# Vitulus_mower_control_2021-01-18.net
KiCad netlist of a schematic drawn in EasyEDA
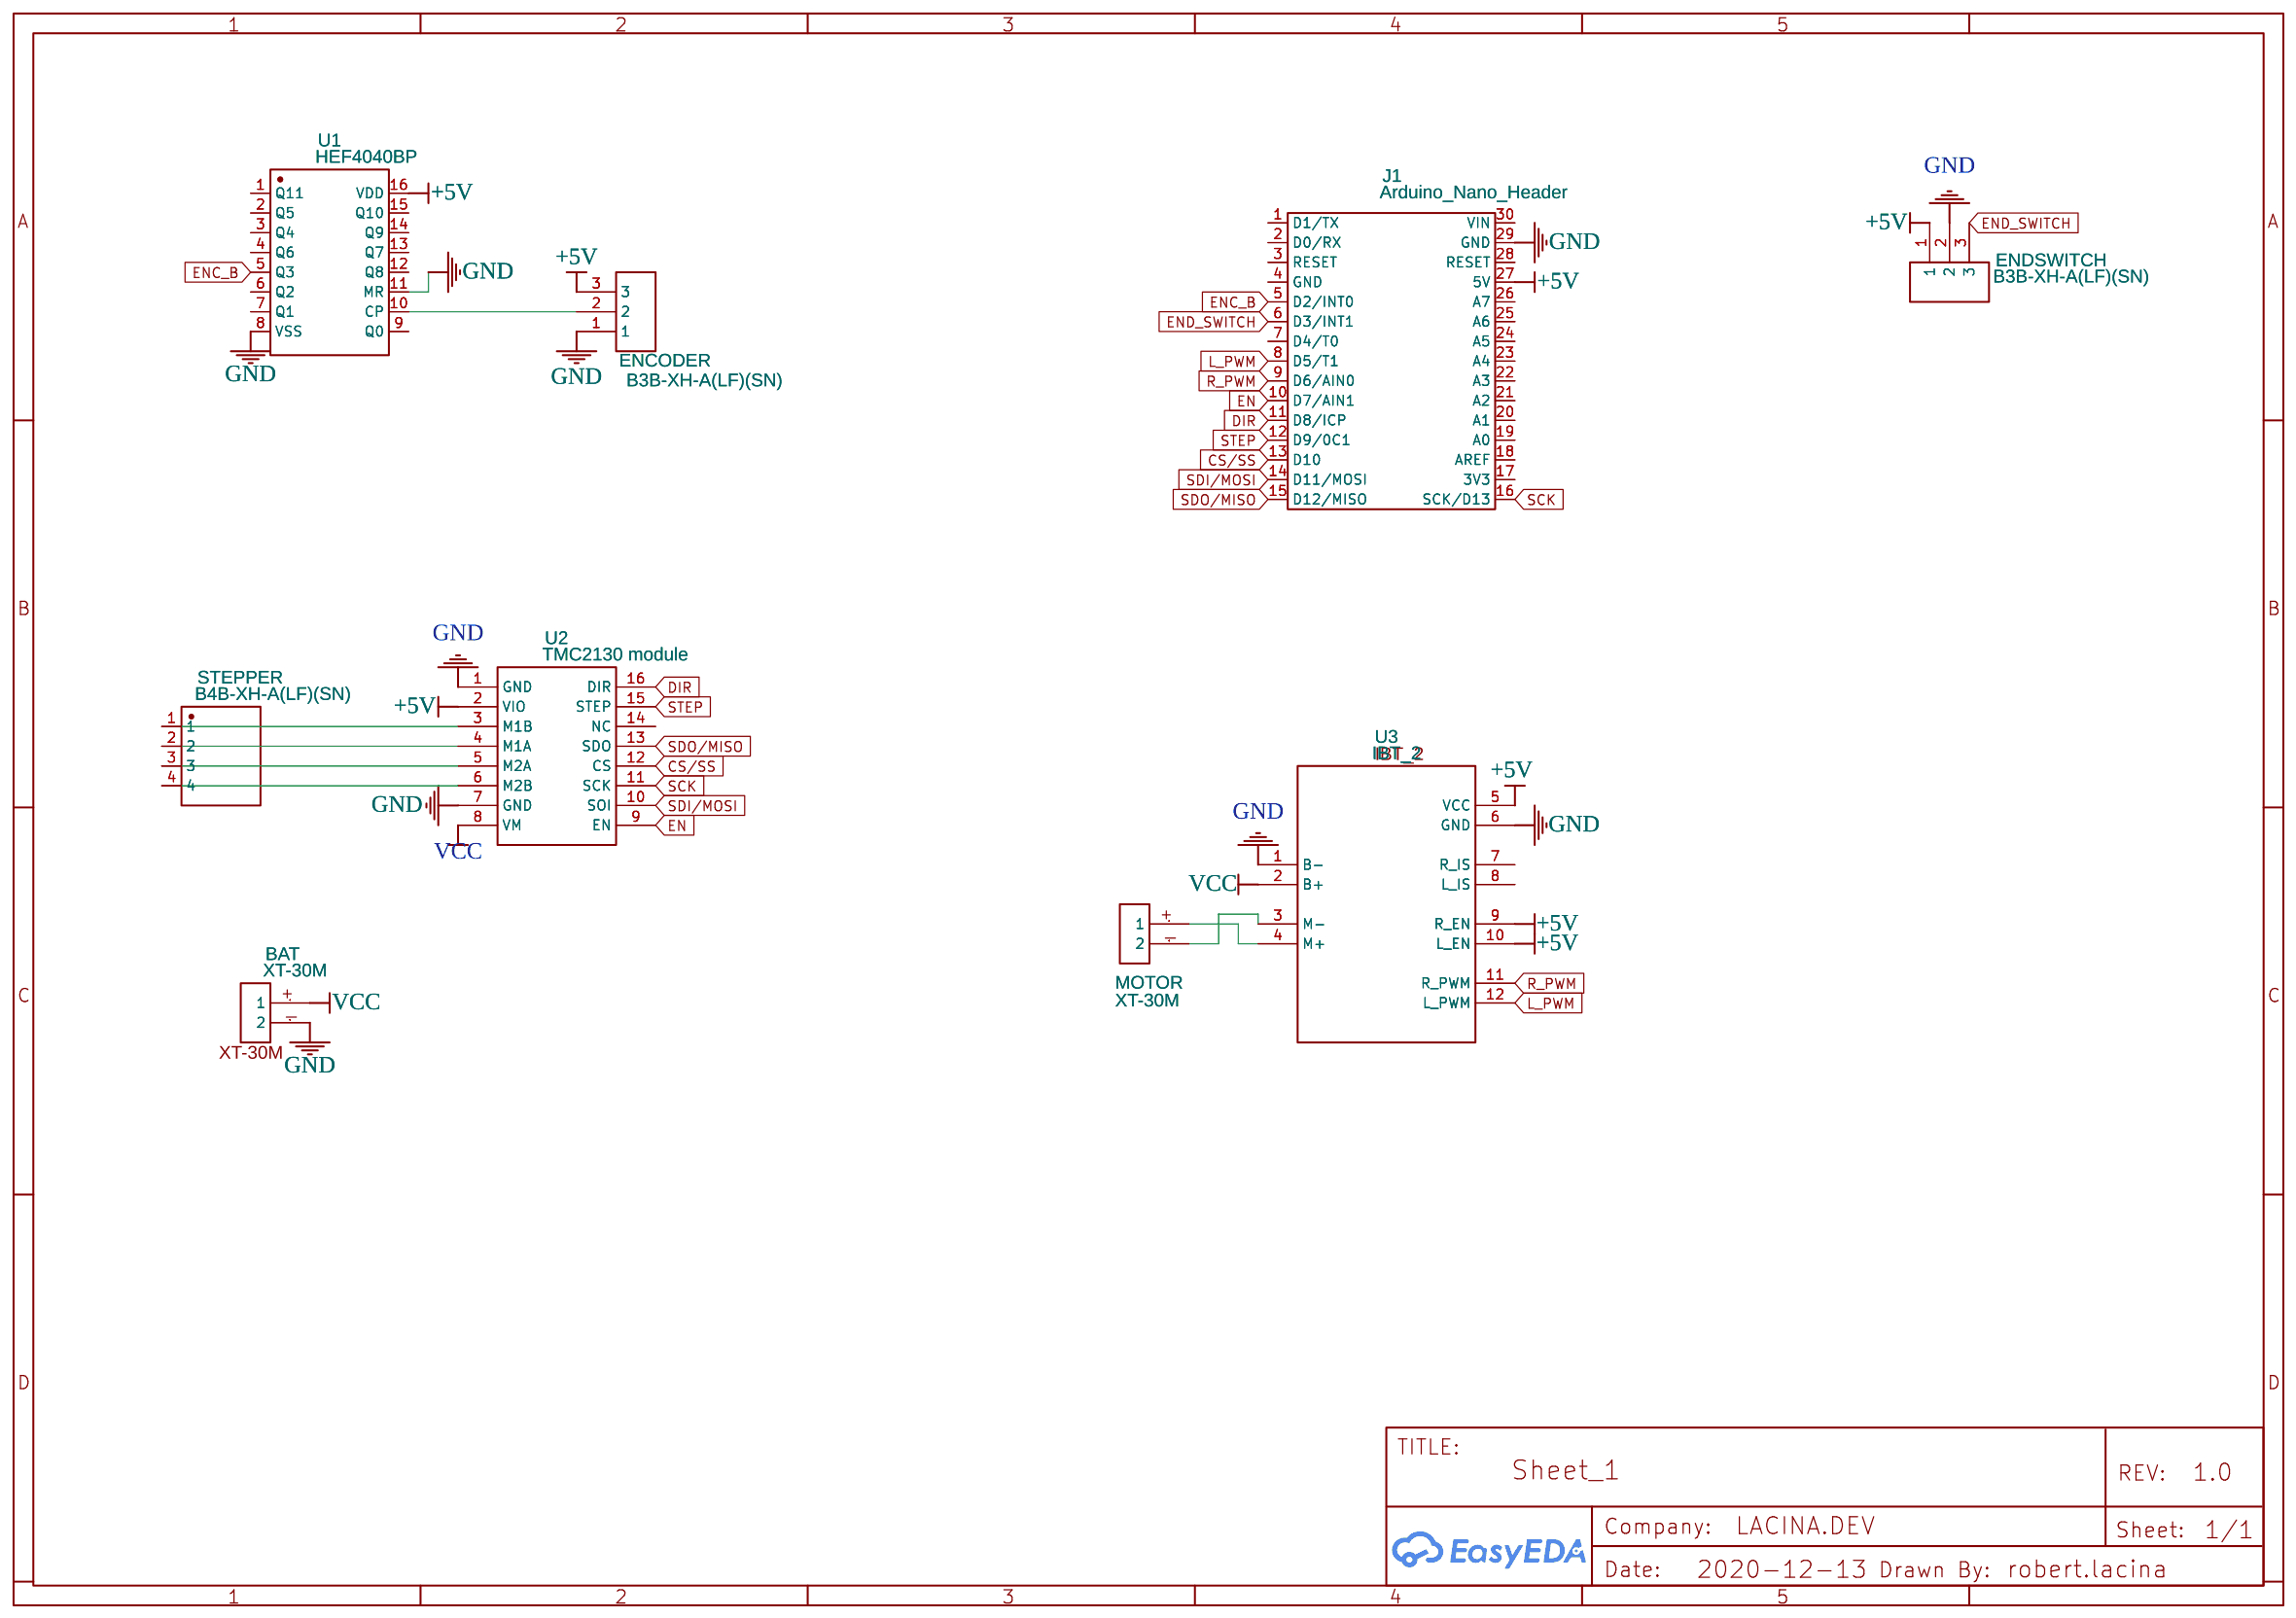
[diagram p0: schematic sheet]

(export (version "E")
  (design (tool "Eeschema 10.0.6"))
  (components
    (comp (ref "BAT") (value "XT-30M") (libsource (lib "") (part "XT-30M_1")))
    (comp (ref "ENCODER")
      (value "B3B-XH-A(LF)(SN)")
      (fields (field (name "BOM_Supplier Part") "C144394"))
      (libsource (lib "") (part "B3B-XH-A(LF)(SN)_1"))
    )
    (comp (ref "ENDSWITCH")
      (value "B3B-XH-A(LF)(SN)")
      (fields (field (name "BOM_Supplier Part") "C144394"))
      (libsource (lib "") (part "B3B-XH-A(LF)(SN)"))
    )
    (comp (ref "J1") (value "Arduino_Nano_Header") (libsource (lib "") (part "Arduino_Nano_Header")))
    (comp (ref "MOTOR") (value "XT-30M") (libsource (lib "") (part "XT-30M")))
    (comp (ref "STEPPER")
      (value "B4B-XH-A(LF)(SN)")
      (fields (field (name "BOM_Supplier Part") "C144395"))
      (libsource (lib "") (part "B4B-XH-A(LF)(SN)"))
    )
    (comp (ref "U1") (value "HEF4040BP") (libsource (lib "") (part "HEF4040BP")))
    (comp (ref "U2") (value "TMC2130 module") (libsource (lib "") (part "TMC2130 module")))
    (comp (ref "U3") (value "IBT_2") (libsource (lib "") (part "IBT_2")))
  )
  (nets
    (net (code "1") (name "+5V") (class "Default")
      (node (ref "ENCODER") (pin "3") (pinfunction "3_3") (pintype "unspecified"))
      (node (ref "ENDSWITCH") (pin "1") (pinfunction "1_1") (pintype "unspecified"))
      (node (ref "J1") (pin "27") (pinfunction "5V_27") (pintype "unspecified"))
      (node (ref "U1") (pin "16") (pinfunction "VDD_16") (pintype "unspecified"))
      (node (ref "U2") (pin "2") (pinfunction "VIO_2") (pintype "unspecified"))
      (node (ref "U3") (pin "10") (pinfunction "L_EN_10") (pintype "unspecified"))
      (node (ref "U3") (pin "5") (pinfunction "VCC_5") (pintype "unspecified"))
      (node (ref "U3") (pin "9") (pinfunction "R_EN_9") (pintype "unspecified"))
    )
    (net (code "2") (name "CS{slash}SS") (class "Default")
      (node (ref "J1") (pin "13") (pinfunction "D10_13") (pintype "unspecified"))
      (node (ref "U2") (pin "12") (pinfunction "CS_12") (pintype "unspecified"))
    )
    (net (code "3") (name "DIR") (class "Default")
      (node (ref "J1") (pin "11") (pinfunction "D8/ICP_11") (pintype "unspecified"))
      (node (ref "U2") (pin "16") (pinfunction "DIR_16") (pintype "unspecified"))
    )
    (net (code "4") (name "EN") (class "Default")
      (node (ref "J1") (pin "10") (pinfunction "D7/AIN1_10") (pintype "unspecified"))
      (node (ref "U2") (pin "9") (pinfunction "EN_9") (pintype "unspecified"))
    )
    (net (code "5") (name "ENC_B") (class "Default")
      (node (ref "J1") (pin "5") (pinfunction "D2/INT0_5") (pintype "unspecified"))
      (node (ref "U1") (pin "5") (pinfunction "Q3_5") (pintype "unspecified"))
    )
    (net (code "6") (name "END_SWITCH") (class "Default")
      (node (ref "ENDSWITCH") (pin "3") (pinfunction "3_3") (pintype "unspecified"))
      (node (ref "J1") (pin "6") (pinfunction "D3/INT1_6") (pintype "unspecified"))
    )
    (net (code "7") (name "GND") (class "Default")
      (node (ref "BAT") (pin "2") (pinfunction "2_2") (pintype "unspecified"))
      (node (ref "ENCODER") (pin "1") (pinfunction "1_1") (pintype "unspecified"))
      (node (ref "ENDSWITCH") (pin "2") (pinfunction "2_2") (pintype "unspecified"))
      (node (ref "J1") (pin "29") (pinfunction "GND_29") (pintype "unspecified"))
      (node (ref "U1") (pin "11") (pinfunction "MR_11") (pintype "unspecified"))
      (node (ref "U1") (pin "8") (pinfunction "VSS_8") (pintype "unspecified"))
      (node (ref "U2") (pin "1") (pinfunction "GND_1") (pintype "unspecified"))
      (node (ref "U2") (pin "7") (pinfunction "GND_7") (pintype "unspecified"))
      (node (ref "U3") (pin "1") (pinfunction "B-_1") (pintype "unspecified"))
      (node (ref "U3") (pin "6") (pinfunction "GND_6") (pintype "unspecified"))
    )
    (net (code "8") (name "L_PWM") (class "Default")
      (node (ref "J1") (pin "8") (pinfunction "D5/T1_8") (pintype "unspecified"))
      (node (ref "U3") (pin "12") (pinfunction "L_PWM_12") (pintype "unspecified"))
    )
    (net (code "9") (name "Net-(U1-CP)") (class "Default")
      (node (ref "ENCODER") (pin "2") (pinfunction "2_2") (pintype "unspecified"))
      (node (ref "U1") (pin "10") (pinfunction "CP_10") (pintype "unspecified"))
    )
    (net (code "10") (name "Net-(U2-M1A)") (class "Default")
      (node (ref "STEPPER") (pin "2") (pinfunction "2_2") (pintype "unspecified"))
      (node (ref "U2") (pin "4") (pinfunction "M1A_4") (pintype "unspecified"))
    )
    (net (code "11") (name "Net-(U2-M1B)") (class "Default")
      (node (ref "STEPPER") (pin "1") (pinfunction "1_1") (pintype "unspecified"))
      (node (ref "U2") (pin "3") (pinfunction "M1B_3") (pintype "unspecified"))
    )
    (net (code "12") (name "Net-(U2-M2A)") (class "Default")
      (node (ref "STEPPER") (pin "3") (pinfunction "3_3") (pintype "unspecified"))
      (node (ref "U2") (pin "5") (pinfunction "M2A_5") (pintype "unspecified"))
    )
    (net (code "13") (name "Net-(U2-M2B)") (class "Default")
      (node (ref "STEPPER") (pin "4") (pinfunction "4_4") (pintype "unspecified"))
      (node (ref "U2") (pin "6") (pinfunction "M2B_6") (pintype "unspecified"))
    )
    (net (code "14") (name "Net-(U3-M+)") (class "Default")
      (node (ref "MOTOR") (pin "1") (pinfunction "1_1") (pintype "unspecified"))
      (node (ref "U3") (pin "4") (pinfunction "M+_4") (pintype "unspecified"))
    )
    (net (code "15") (name "Net-(U3-M-)") (class "Default")
      (node (ref "MOTOR") (pin "2") (pinfunction "2_2") (pintype "unspecified"))
      (node (ref "U3") (pin "3") (pinfunction "M-_3") (pintype "unspecified"))
    )
    (net (code "16") (name "R_PWM") (class "Default")
      (node (ref "J1") (pin "9") (pinfunction "D6/AIN0_9") (pintype "unspecified"))
      (node (ref "U3") (pin "11") (pinfunction "R_PWM_11") (pintype "unspecified"))
    )
    (net (code "17") (name "SCK") (class "Default")
      (node (ref "J1") (pin "16") (pinfunction "SCK/D13_16") (pintype "unspecified"))
      (node (ref "U2") (pin "11") (pinfunction "SCK_11") (pintype "unspecified"))
    )
    (net (code "18") (name "SDI{slash}MOSI") (class "Default")
      (node (ref "J1") (pin "14") (pinfunction "D11/MOSI_14") (pintype "unspecified"))
      (node (ref "U2") (pin "10") (pinfunction "SOI_10") (pintype "unspecified"))
    )
    (net (code "19") (name "SDO{slash}MISO") (class "Default")
      (node (ref "J1") (pin "15") (pinfunction "D12/MISO_15") (pintype "unspecified"))
      (node (ref "U2") (pin "13") (pinfunction "SDO_13") (pintype "unspecified"))
    )
    (net (code "20") (name "STEP") (class "Default")
      (node (ref "J1") (pin "12") (pinfunction "D9/0C1_12") (pintype "unspecified"))
      (node (ref "U2") (pin "15") (pinfunction "STEP_15") (pintype "unspecified"))
    )
    (net (code "21") (name "VCC") (class "Default")
      (node (ref "BAT") (pin "1") (pinfunction "1_1") (pintype "unspecified"))
      (node (ref "U2") (pin "8") (pinfunction "VM_8") (pintype "unspecified"))
      (node (ref "U3") (pin "2") (pinfunction "B+_2") (pintype "unspecified"))
    )
    (net (code "22") (name "unconnected-(J1-3V3-Pad17)") (class "Default")
      (node (ref "J1") (pin "17") (pinfunction "3V3_17") (pintype "unspecified"))
    )
    (net (code "23") (name "unconnected-(J1-A0-Pad19)") (class "Default")
      (node (ref "J1") (pin "19") (pinfunction "A0_19") (pintype "unspecified"))
    )
    (net (code "24") (name "unconnected-(J1-A1-Pad20)") (class "Default")
      (node (ref "J1") (pin "20") (pinfunction "A1_20") (pintype "unspecified"))
    )
    (net (code "25") (name "unconnected-(J1-A2-Pad21)") (class "Default")
      (node (ref "J1") (pin "21") (pinfunction "A2_21") (pintype "unspecified"))
    )
    (net (code "26") (name "unconnected-(J1-A3-Pad22)") (class "Default")
      (node (ref "J1") (pin "22") (pinfunction "A3_22") (pintype "unspecified"))
    )
    (net (code "27") (name "unconnected-(J1-A4-Pad23)") (class "Default")
      (node (ref "J1") (pin "23") (pinfunction "A4_23") (pintype "unspecified"))
    )
    (net (code "28") (name "unconnected-(J1-A5-Pad24)") (class "Default")
      (node (ref "J1") (pin "24") (pinfunction "A5_24") (pintype "unspecified"))
    )
    (net (code "29") (name "unconnected-(J1-A6-Pad25)") (class "Default")
      (node (ref "J1") (pin "25") (pinfunction "A6_25") (pintype "unspecified"))
    )
    (net (code "30") (name "unconnected-(J1-A7-Pad26)") (class "Default")
      (node (ref "J1") (pin "26") (pinfunction "A7_26") (pintype "unspecified"))
    )
    (net (code "31") (name "unconnected-(J1-AREF-Pad18)") (class "Default")
      (node (ref "J1") (pin "18") (pinfunction "AREF_18") (pintype "unspecified"))
    )
    (net (code "32") (name "unconnected-(J1-D0{slash}RX-Pad2)") (class "Default")
      (node (ref "J1") (pin "2") (pinfunction "D0/RX_2") (pintype "unspecified"))
    )
    (net (code "33") (name "unconnected-(J1-D1{slash}TX-Pad1)") (class "Default")
      (node (ref "J1") (pin "1") (pinfunction "D1/TX_1") (pintype "unspecified"))
    )
    (net (code "34") (name "unconnected-(J1-D4{slash}T0-Pad7)") (class "Default")
      (node (ref "J1") (pin "7") (pinfunction "D4/T0_7") (pintype "unspecified"))
    )
    (net (code "35") (name "unconnected-(J1-GND-Pad4)") (class "Default")
      (node (ref "J1") (pin "4") (pinfunction "GND_4") (pintype "unspecified"))
    )
    (net (code "36") (name "unconnected-(J1-RESET-Pad3)") (class "Default")
      (node (ref "J1") (pin "3") (pinfunction "RESET_3") (pintype "unspecified"))
    )
    (net (code "37") (name "unconnected-(J1-RESET-Pad28)") (class "Default")
      (node (ref "J1") (pin "28") (pinfunction "RESET_28") (pintype "unspecified"))
    )
    (net (code "38") (name "unconnected-(J1-VIN-Pad30)") (class "Default")
      (node (ref "J1") (pin "30") (pinfunction "VIN_30") (pintype "unspecified"))
    )
    (net (code "39") (name "unconnected-(U1-Q0-Pad9)") (class "Default")
      (node (ref "U1") (pin "9") (pinfunction "Q0_9") (pintype "unspecified"))
    )
    (net (code "40") (name "unconnected-(U1-Q1-Pad7)") (class "Default")
      (node (ref "U1") (pin "7") (pinfunction "Q1_7") (pintype "unspecified"))
    )
    (net (code "41") (name "unconnected-(U1-Q2-Pad6)") (class "Default")
      (node (ref "U1") (pin "6") (pinfunction "Q2_6") (pintype "unspecified"))
    )
    (net (code "42") (name "unconnected-(U1-Q4-Pad3)") (class "Default")
      (node (ref "U1") (pin "3") (pinfunction "Q4_3") (pintype "unspecified"))
    )
    (net (code "43") (name "unconnected-(U1-Q5-Pad2)") (class "Default")
      (node (ref "U1") (pin "2") (pinfunction "Q5_2") (pintype "unspecified"))
    )
    (net (code "44") (name "unconnected-(U1-Q6-Pad4)") (class "Default")
      (node (ref "U1") (pin "4") (pinfunction "Q6_4") (pintype "unspecified"))
    )
    (net (code "45") (name "unconnected-(U1-Q7-Pad13)") (class "Default")
      (node (ref "U1") (pin "13") (pinfunction "Q7_13") (pintype "unspecified"))
    )
    (net (code "46") (name "unconnected-(U1-Q8-Pad12)") (class "Default")
      (node (ref "U1") (pin "12") (pinfunction "Q8_12") (pintype "unspecified"))
    )
    (net (code "47") (name "unconnected-(U1-Q9-Pad14)") (class "Default")
      (node (ref "U1") (pin "14") (pinfunction "Q9_14") (pintype "unspecified"))
    )
    (net (code "48") (name "unconnected-(U1-Q10-Pad15)") (class "Default")
      (node (ref "U1") (pin "15") (pinfunction "Q10_15") (pintype "unspecified"))
    )
    (net (code "49") (name "unconnected-(U1-Q11-Pad1)") (class "Default")
      (node (ref "U1") (pin "1") (pinfunction "Q11_1") (pintype "unspecified"))
    )
    (net (code "50") (name "unconnected-(U2-NC-Pad14)") (class "Default")
      (node (ref "U2") (pin "14") (pinfunction "NC_14") (pintype "unspecified"))
    )
    (net (code "51") (name "unconnected-(U3-L_IS-Pad8)") (class "Default")
      (node (ref "U3") (pin "8") (pinfunction "L_IS_8") (pintype "unspecified"))
    )
    (net (code "52") (name "unconnected-(U3-R_IS-Pad7)") (class "Default")
      (node (ref "U3") (pin "7") (pinfunction "R_IS_7") (pintype "unspecified"))
    )
  )
)
